# Sheet1.net
KiCad netlist of a schematic drawn in Altium Designer
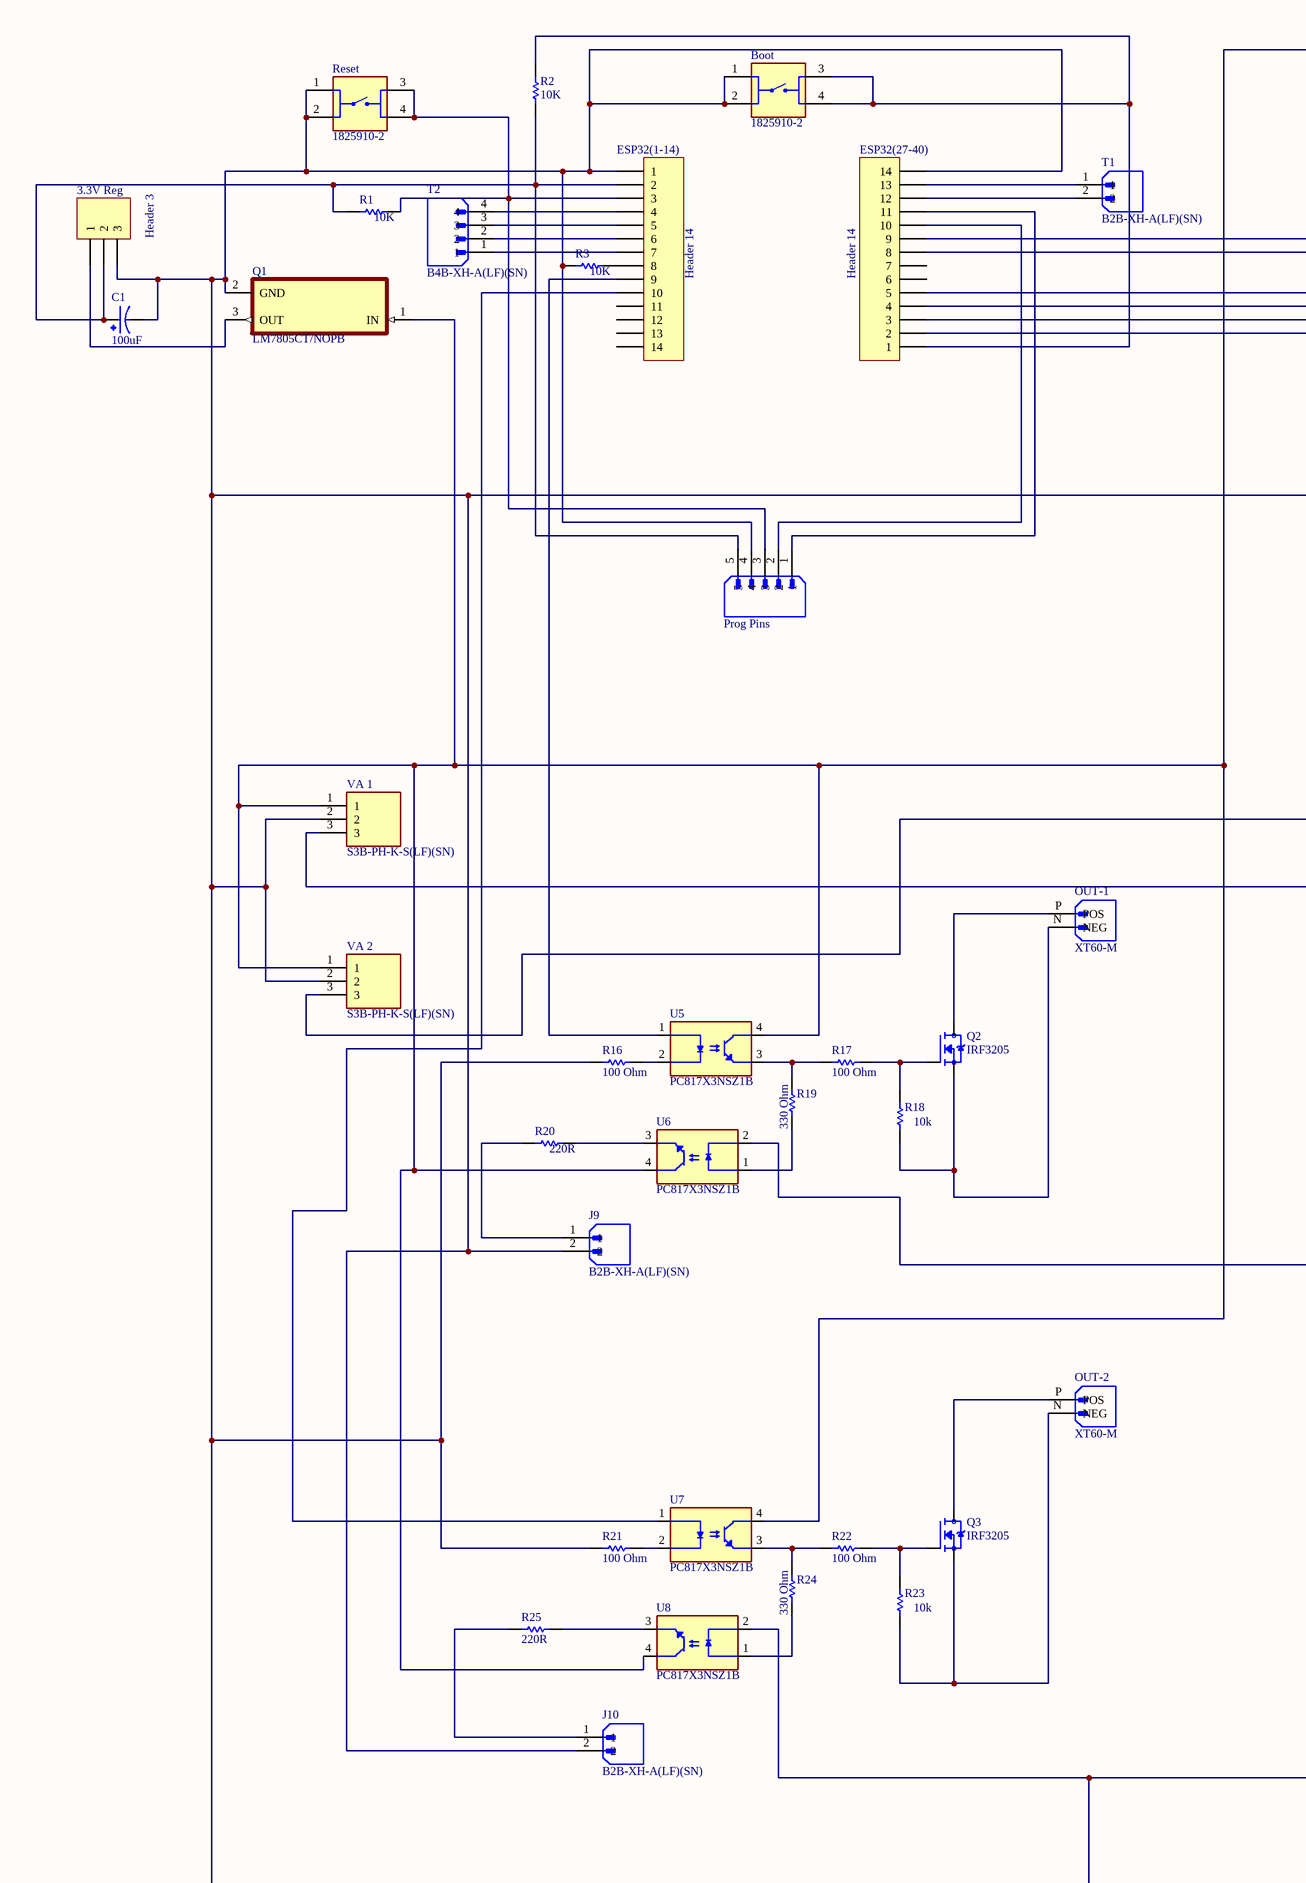
[diagram p0: Sheet1.SchDoc, left]
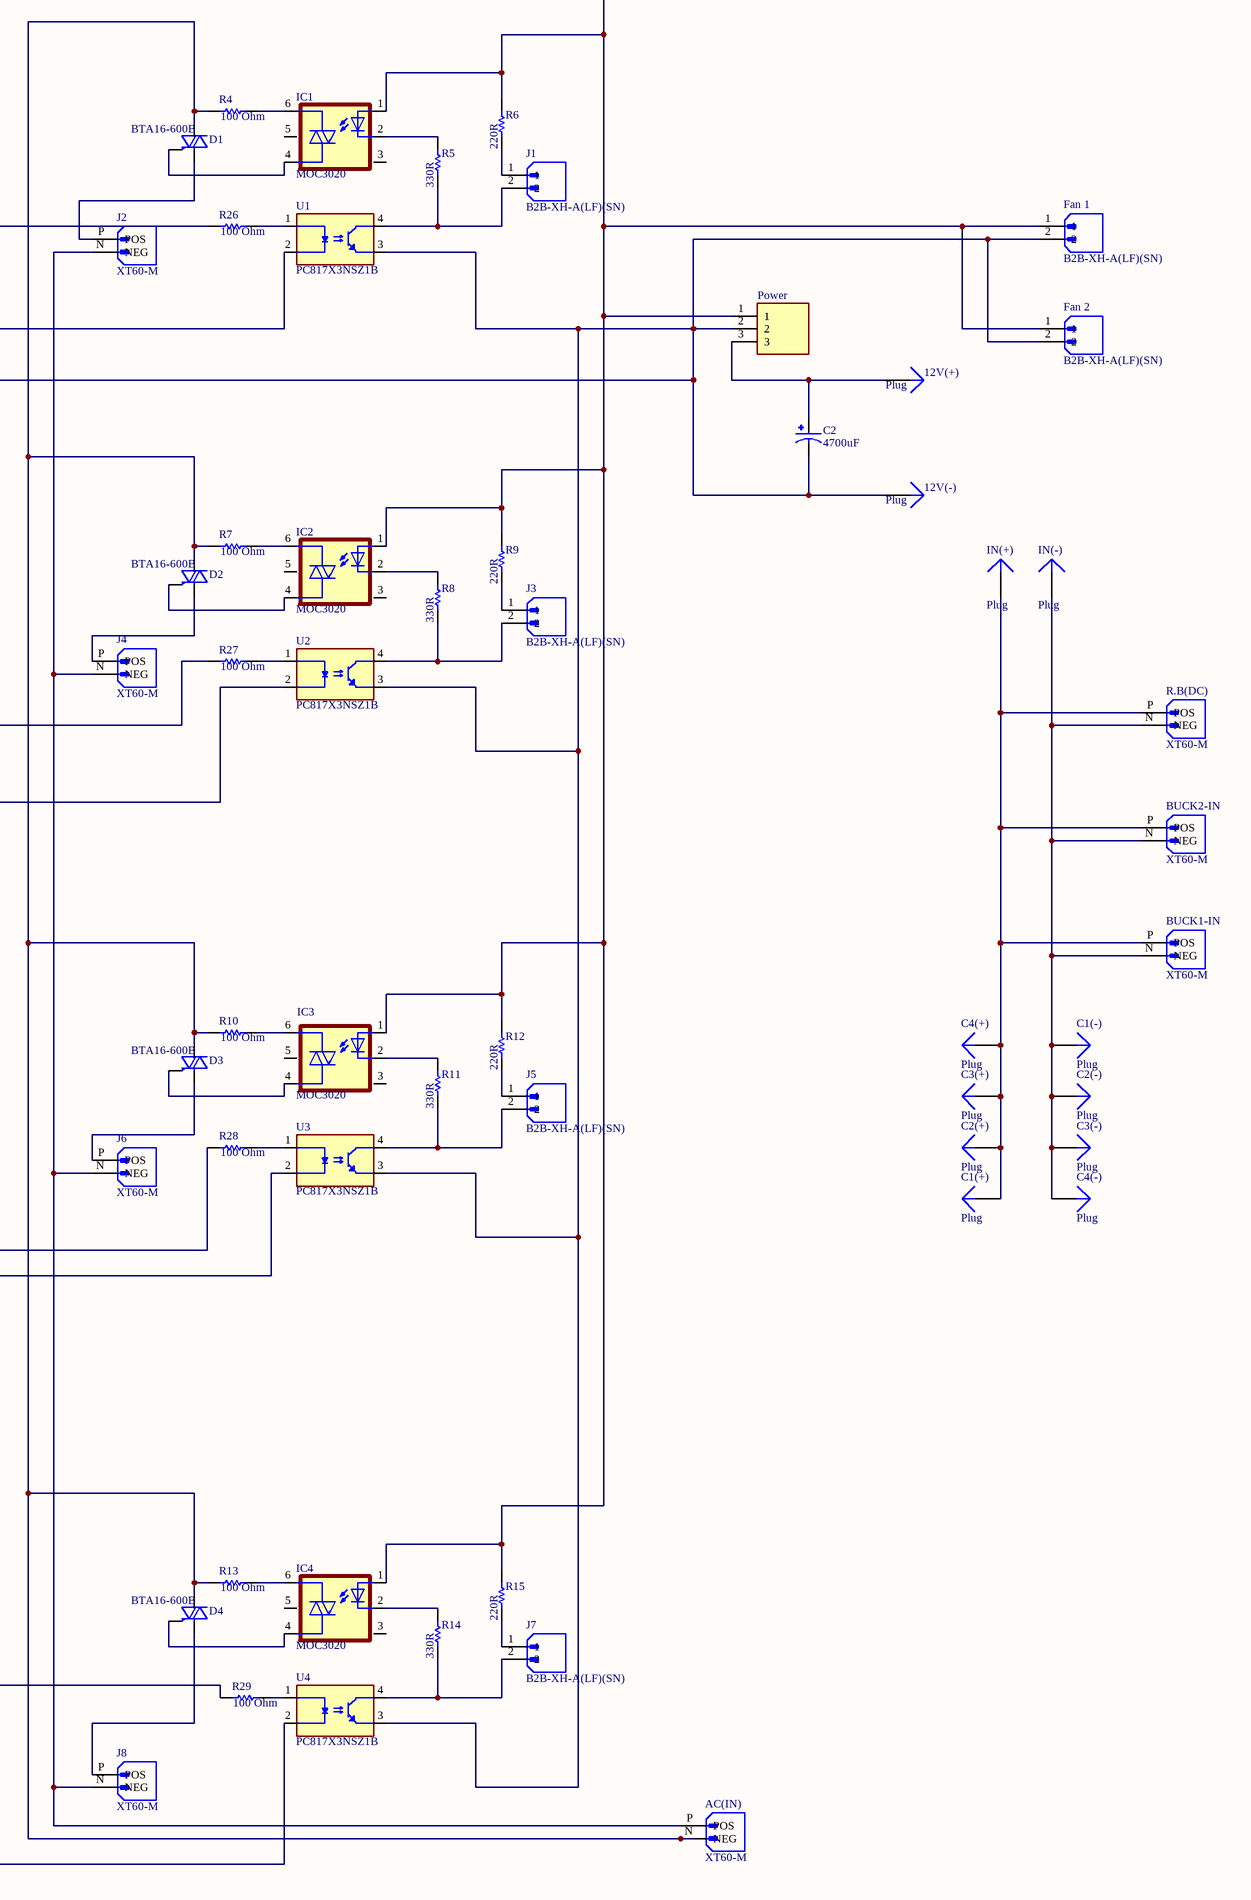
[diagram p1: Sheet1.SchDoc, right]

(export (version "E")
  (design (tool "Eeschema 10.0.6"))
  (components
    (comp (ref "3.3V Reg")
      (value "Header 3")
      (footprint "HDR1X3")
      (description "Header, 3-Pin")
      (fields (field (name "PUBLISHER") "Altium Limited"))
      (libsource (lib "Miscellaneous Connectors") (part "Header 3"))
    )
    (comp (ref "12V(+)")
      (value "Plug")
      (footprint "PIN1")
      (fields (field (name "PUBLISHER") "Altium Limited"))
      (libsource (lib "Miscellaneous Connectors") (part "Plug"))
    )
    (comp (ref "12V(-)")
      (value "Plug")
      (footprint "PIN1")
      (fields (field (name "PUBLISHER") "Altium Limited"))
      (libsource (lib "Miscellaneous Connectors") (part "Plug"))
    )
    (comp (ref "AC(IN)")
      (value "XT60-M")
      (footprint "AMASS_XT60-M")
      (description "Plug; DC supply; XT60; male; PIN: 2; for cable; soldered; 30A; 500V")
      (fields (field (name "MF") "AMASS"))
      (libsource (lib "XT60-M") (part "XT60-M"))
    )
    (comp (ref "Boot")
      (value "1825910-2")
      (footprint "TE_1825910-2")
      (description "50 mA SPST Round Actuator 160 Gram Force Tactile Pushbutton Switch")
      (fields (field (name "MF") "TE Connectivity"))
      (libsource (lib "push button") (part "1825910-2"))
    )
    (comp (ref "BUCK1-IN")
      (value "XT60-M")
      (footprint "AMASS_XT60-M")
      (description "Plug; DC supply; XT60; male; PIN: 2; for cable; soldered; 30A; 500V")
      (fields (field (name "MF") "AMASS"))
      (libsource (lib "XT60-M") (part "XT60-M"))
    )
    (comp (ref "BUCK2-IN")
      (value "XT60-M")
      (footprint "AMASS_XT60-M")
      (description "Plug; DC supply; XT60; male; PIN: 2; for cable; soldered; 30A; 500V")
      (fields (field (name "MF") "AMASS"))
      (libsource (lib "XT60-M") (part "XT60-M"))
    )
    (comp (ref "C1")
      (value "100uF")
      (footprint "CAPPRD250W50D630H1500")
      (description "CAP ALUM 100UF 20% 25V RADIAL")
      (fields (field (name "MP") "EEUEB1E101") (field (name "MF") "Panasonic"))
      (libsource (lib "100uF") (part "EEUEB1E101"))
    )
    (comp (ref "C1(+)")
      (value "Plug")
      (footprint "PIN1")
      (fields (field (name "PUBLISHER") "Altium Limited"))
      (libsource (lib "Miscellaneous Connectors") (part "Plug"))
    )
    (comp (ref "C1(-)")
      (value "Plug")
      (footprint "PIN1")
      (fields (field (name "PUBLISHER") "Altium Limited"))
      (libsource (lib "Miscellaneous Connectors") (part "Plug"))
    )
    (comp (ref "C2")
      (value "4700uF")
      (footprint "CAPPRD750W80D1800H3150")
      (description "CAP ALUM 4700UF 20% 25V RADIAL")
      (fields (field (name "MF") "Panasonic") (field (name "MP") "EEU-TP1E472"))
      (libsource (lib "4700uF") (part "EEUTP1E472"))
    )
    (comp (ref "C2(+)")
      (value "Plug")
      (footprint "PIN1")
      (fields (field (name "PUBLISHER") "Altium Limited"))
      (libsource (lib "Miscellaneous Connectors") (part "Plug"))
    )
    (comp (ref "C2(-)")
      (value "Plug")
      (footprint "PIN1")
      (fields (field (name "PUBLISHER") "Altium Limited"))
      (libsource (lib "Miscellaneous Connectors") (part "Plug"))
    )
    (comp (ref "C3(+)")
      (value "Plug")
      (footprint "PIN1")
      (fields (field (name "PUBLISHER") "Altium Limited"))
      (libsource (lib "Miscellaneous Connectors") (part "Plug"))
    )
    (comp (ref "C3(-)")
      (value "Plug")
      (footprint "PIN1")
      (fields (field (name "PUBLISHER") "Altium Limited"))
      (libsource (lib "Miscellaneous Connectors") (part "Plug"))
    )
    (comp (ref "C4(+)")
      (value "Plug")
      (footprint "PIN1")
      (fields (field (name "PUBLISHER") "Altium Limited"))
      (libsource (lib "Miscellaneous Connectors") (part "Plug"))
    )
    (comp (ref "C4(-)")
      (value "Plug")
      (footprint "PIN1")
      (fields (field (name "PUBLISHER") "Altium Limited"))
      (libsource (lib "Miscellaneous Connectors") (part "Plug"))
    )
    (comp (ref "D1")
      (value "BTA16-600B")
      (footprint "TO255P1040X460X1975-3")
      (description "TRIAC Standard 600V 16A Through Hole IITO-220E")
      (libsource (lib "BTA16-600B") (part "BTA16-600B"))
    )
    (comp (ref "D2")
      (value "BTA16-600B")
      (footprint "TO255P1040X460X1975-3")
      (description "TRIAC Standard 600V 16A Through Hole IITO-220E")
      (libsource (lib "BTA16-600B") (part "BTA16-600B"))
    )
    (comp (ref "D3")
      (value "BTA16-600B")
      (footprint "TO255P1040X460X1975-3")
      (description "TRIAC Standard 600V 16A Through Hole IITO-220E")
      (libsource (lib "BTA16-600B") (part "BTA16-600B"))
    )
    (comp (ref "D4")
      (value "BTA16-600B")
      (footprint "TO255P1040X460X1975-3")
      (description "TRIAC Standard 600V 16A Through Hole IITO-220E")
      (libsource (lib "BTA16-600B") (part "BTA16-600B"))
    )
    (comp (ref "ESP32(1-14)")
      (value "Header 14")
      (footprint "HDR1X14")
      (description "Header, 14-Pin")
      (fields (field (name "PUBLISHER") "Altium Limited"))
      (libsource (lib "Miscellaneous Connectors") (part "Header 14"))
    )
    (comp (ref "ESP32(27-40)")
      (value "Header 14")
      (footprint "HDR1X14")
      (description "Header, 14-Pin")
      (fields (field (name "PUBLISHER") "Altium Limited"))
      (libsource (lib "") (part "Header 14_1"))
    )
    (comp (ref "Fan 1")
      (value "B2B-XH-A(LF)(SN)")
      (footprint "JST_B2B-XH-A(LF)(SN)")
      (description "Connector Header Through Hole 2 position 0.098 (2.50mm)")
      (fields (field (name "MF") "JST Sales America Inc."))
      (libsource (lib "JST-2") (part "B2B-XH-A(LF)(SN)"))
    )
    (comp (ref "Fan 2")
      (value "B2B-XH-A(LF)(SN)")
      (footprint "JST_B2B-XH-A(LF)(SN)")
      (description "Connector Header Through Hole 2 position 0.098 (2.50mm)")
      (fields (field (name "MF") "JST Sales America Inc."))
      (libsource (lib "JST-2") (part "B2B-XH-A(LF)(SN)"))
    )
    (comp (ref "IC1")
      (value "MOC3020")
      (footprint "DIL06-A")
      (description "Optoisolator Triac Output 5300Vrms 1 Channel 6-DIP")
      (fields (field (name "MF") "ON Semiconductor"))
      (libsource (lib "MOC3020") (part "MOC3020"))
    )
    (comp (ref "IC2")
      (value "MOC3020")
      (footprint "DIL06-A")
      (description "Optoisolator Triac Output 5300Vrms 1 Channel 6-DIP")
      (fields (field (name "MF") "ON Semiconductor"))
      (libsource (lib "MOC3020") (part "MOC3020"))
    )
    (comp (ref "IC3")
      (value "MOC3020")
      (footprint "DIL06-A")
      (description "Optoisolator Triac Output 5300Vrms 1 Channel 6-DIP")
      (fields (field (name "MF") "ON Semiconductor"))
      (libsource (lib "MOC3020") (part "MOC3020"))
    )
    (comp (ref "IC4")
      (value "MOC3020")
      (footprint "DIL06-A")
      (description "Optoisolator Triac Output 5300Vrms 1 Channel 6-DIP")
      (fields (field (name "MF") "ON Semiconductor"))
      (libsource (lib "MOC3020") (part "MOC3020"))
    )
    (comp (ref "IN(+)")
      (value "Plug")
      (footprint "PIN1")
      (fields (field (name "PUBLISHER") "Altium Limited"))
      (libsource (lib "Miscellaneous Connectors") (part "Plug"))
    )
    (comp (ref "IN(-)")
      (value "Plug")
      (footprint "PIN1")
      (fields (field (name "PUBLISHER") "Altium Limited"))
      (libsource (lib "Miscellaneous Connectors") (part "Plug"))
    )
    (comp (ref "J1")
      (value "B2B-XH-A(LF)(SN)")
      (footprint "JST_B2B-XH-A(LF)(SN)")
      (description "Connector Header Through Hole 2 position 0.098 (2.50mm)")
      (fields (field (name "MF") "JST Sales America Inc."))
      (libsource (lib "JST-2") (part "B2B-XH-A(LF)(SN)"))
    )
    (comp (ref "J2")
      (value "XT60-M")
      (footprint "AMASS_XT60-M")
      (description "Plug; DC supply; XT60; male; PIN: 2; for cable; soldered; 30A; 500V")
      (fields (field (name "MF") "AMASS"))
      (libsource (lib "XT60-M") (part "XT60-M"))
    )
    (comp (ref "J3")
      (value "B2B-XH-A(LF)(SN)")
      (footprint "JST_B2B-XH-A(LF)(SN)")
      (description "Connector Header Through Hole 2 position 0.098 (2.50mm)")
      (fields (field (name "MF") "JST Sales America Inc."))
      (libsource (lib "JST-2") (part "B2B-XH-A(LF)(SN)"))
    )
    (comp (ref "J4")
      (value "XT60-M")
      (footprint "AMASS_XT60-M")
      (description "Plug; DC supply; XT60; male; PIN: 2; for cable; soldered; 30A; 500V")
      (fields (field (name "MF") "AMASS"))
      (libsource (lib "XT60-M") (part "XT60-M"))
    )
    (comp (ref "J5")
      (value "B2B-XH-A(LF)(SN)")
      (footprint "JST_B2B-XH-A(LF)(SN)")
      (description "Connector Header Through Hole 2 position 0.098 (2.50mm)")
      (fields (field (name "MF") "JST Sales America Inc."))
      (libsource (lib "JST-2") (part "B2B-XH-A(LF)(SN)"))
    )
    (comp (ref "J6")
      (value "XT60-M")
      (footprint "AMASS_XT60-M")
      (description "Plug; DC supply; XT60; male; PIN: 2; for cable; soldered; 30A; 500V")
      (fields (field (name "MF") "AMASS"))
      (libsource (lib "XT60-M") (part "XT60-M"))
    )
    (comp (ref "J7")
      (value "B2B-XH-A(LF)(SN)")
      (footprint "JST_B2B-XH-A(LF)(SN)")
      (description "Connector Header Through Hole 2 position 0.098 (2.50mm)")
      (fields (field (name "MF") "JST Sales America Inc."))
      (libsource (lib "JST-2") (part "B2B-XH-A(LF)(SN)"))
    )
    (comp (ref "J8")
      (value "XT60-M")
      (footprint "AMASS_XT60-M")
      (description "Plug; DC supply; XT60; male; PIN: 2; for cable; soldered; 30A; 500V")
      (fields (field (name "MF") "AMASS"))
      (libsource (lib "XT60-M") (part "XT60-M"))
    )
    (comp (ref "J9")
      (value "B2B-XH-A(LF)(SN)")
      (footprint "JST_B2B-XH-A(LF)(SN)")
      (description "Connector Header Through Hole 2 position 0.098 (2.50mm)")
      (fields (field (name "MF") "JST Sales America Inc."))
      (libsource (lib "JST-2") (part "B2B-XH-A(LF)(SN)"))
    )
    (comp (ref "J10")
      (value "B2B-XH-A(LF)(SN)")
      (footprint "JST_B2B-XH-A(LF)(SN)")
      (description "Connector Header Through Hole 2 position 0.098 (2.50mm)")
      (fields (field (name "MF") "JST Sales America Inc."))
      (libsource (lib "JST-2") (part "B2B-XH-A(LF)(SN)"))
    )
    (comp (ref "OUT-1")
      (value "XT60-M")
      (footprint "AMASS_XT60-M")
      (description "Plug; DC supply; XT60; male; PIN: 2; for cable; soldered; 30A; 500V")
      (fields (field (name "MF") "AMASS"))
      (libsource (lib "XT60-M") (part "XT60-M"))
    )
    (comp (ref "OUT-2")
      (value "XT60-M")
      (footprint "AMASS_XT60-M")
      (description "Plug; DC supply; XT60; male; PIN: 2; for cable; soldered; 30A; 500V")
      (fields (field (name "MF") "AMASS"))
      (libsource (lib "XT60-M") (part "XT60-M"))
    )
    (comp (ref "Power")
      (value "~")
      (footprint "JST_S3B-PH-K-S(LF)(SN)")
      (description "Connector Header Through Hole, Right Angle 3 position 0.079\" (2.00mm)")
      (fields (field (name "MP") "S3B-PH-K-S(LF)(SN)"))
      (libsource (lib "JST-3") (part "S3B-PH-K-S(LF)(SN)"))
    )
    (comp (ref "Prog Pins")
      (value "~")
      (footprint "JST_B5B-XH-A(LF)(SN)")
      (description "Connector Header Through Hole 5 position 0.098 (2.50mm)")
      (fields (field (name "MP") "B5B-XH-A(LF)(SN)") (field (name "MF") "JST Sales America Inc."))
      (libsource (lib "JST-5") (part "B5B-XH-A(LF)(SN)"))
    )
    (comp (ref "Q1")
      (value "LM7805CT/NOPB")
      (footprint "TO254P1054X470X1955-3")
      (libsource (lib "LM7805CT_NOPB") (part "LM7805CT/NOPB"))
    )
    (comp (ref "Q2")
      (value "IRF3205")
      (footprint "TO254P1041X444X2933-3")
      (description "N-Channel 55V 110A (Tc) 200W (Tc) Through Hole TO-220AB")
      (fields (field (name "MF") "Infineon Technologies"))
      (libsource (lib "IRF3205") (part "IRF3205"))
    )
    (comp (ref "Q3")
      (value "IRF3205")
      (footprint "TO254P1041X444X2933-3")
      (description "N-Channel 55V 110A (Tc) 200W (Tc) Through Hole TO-220AB")
      (fields (field (name "MF") "Infineon Technologies"))
      (libsource (lib "IRF3205") (part "IRF3205"))
    )
    (comp (ref "R.B(DC)")
      (value "XT60-M")
      (footprint "AMASS_XT60-M")
      (description "Plug; DC supply; XT60; male; PIN: 2; for cable; soldered; 30A; 500V")
      (fields (field (name "MF") "AMASS"))
      (libsource (lib "XT60-M") (part "XT60-M"))
    )
    (comp (ref "R1")
      (value "10K")
      (footprint "AXIAL-0.3")
      (description "Resistor")
      (fields (field (name "PUBLISHER") "Altium Limited"))
      (libsource (lib "Miscellaneous Devices") (part "Res1"))
    )
    (comp (ref "R2")
      (value "10K")
      (footprint "AXIAL-0.3")
      (description "Resistor")
      (fields (field (name "PUBLISHER") "Altium Limited"))
      (libsource (lib "Miscellaneous Devices") (part "Res1"))
    )
    (comp (ref "R3")
      (value "10K")
      (footprint "AXIAL-0.3")
      (description "Resistor")
      (fields (field (name "PUBLISHER") "Altium Limited"))
      (libsource (lib "Miscellaneous Devices") (part "Res1"))
    )
    (comp (ref "R4")
      (value "100 Ohm")
      (footprint "AXIAL-0.3")
      (description "Resistor")
      (fields (field (name "PUBLISHER") "Altium Limited"))
      (libsource (lib "Miscellaneous Devices") (part "Res1"))
    )
    (comp (ref "R5")
      (value "330R")
      (footprint "AXIAL-0.3")
      (description "Resistor")
      (fields (field (name "PUBLISHER") "Altium Limited"))
      (libsource (lib "Miscellaneous Devices") (part "Res1"))
    )
    (comp (ref "R6")
      (value "220R")
      (footprint "AXIAL-0.3")
      (description "Resistor")
      (fields (field (name "PUBLISHER") "Altium Limited"))
      (libsource (lib "Miscellaneous Devices") (part "Res1"))
    )
    (comp (ref "R7")
      (value "100 Ohm")
      (footprint "AXIAL-0.3")
      (description "Resistor")
      (fields (field (name "PUBLISHER") "Altium Limited"))
      (libsource (lib "Miscellaneous Devices") (part "Res1"))
    )
    (comp (ref "R8")
      (value "330R")
      (footprint "AXIAL-0.3")
      (description "Resistor")
      (fields (field (name "PUBLISHER") "Altium Limited"))
      (libsource (lib "Miscellaneous Devices") (part "Res1"))
    )
    (comp (ref "R9")
      (value "220R")
      (footprint "AXIAL-0.3")
      (description "Resistor")
      (fields (field (name "PUBLISHER") "Altium Limited"))
      (libsource (lib "Miscellaneous Devices") (part "Res1"))
    )
    (comp (ref "R10")
      (value "100 Ohm")
      (footprint "AXIAL-0.3")
      (description "Resistor")
      (fields (field (name "PUBLISHER") "Altium Limited"))
      (libsource (lib "Miscellaneous Devices") (part "Res1"))
    )
    (comp (ref "R11")
      (value "330R")
      (footprint "AXIAL-0.3")
      (description "Resistor")
      (fields (field (name "PUBLISHER") "Altium Limited"))
      (libsource (lib "Miscellaneous Devices") (part "Res1"))
    )
    (comp (ref "R12")
      (value "220R")
      (footprint "AXIAL-0.3")
      (description "Resistor")
      (fields (field (name "PUBLISHER") "Altium Limited"))
      (libsource (lib "Miscellaneous Devices") (part "Res1"))
    )
    (comp (ref "R13")
      (value "100 Ohm")
      (footprint "AXIAL-0.3")
      (description "Resistor")
      (fields (field (name "PUBLISHER") "Altium Limited"))
      (libsource (lib "Miscellaneous Devices") (part "Res1"))
    )
    (comp (ref "R14")
      (value "330R")
      (footprint "AXIAL-0.3")
      (description "Resistor")
      (fields (field (name "PUBLISHER") "Altium Limited"))
      (libsource (lib "Miscellaneous Devices") (part "Res1"))
    )
    (comp (ref "R15")
      (value "220R")
      (footprint "AXIAL-0.3")
      (description "Resistor")
      (fields (field (name "PUBLISHER") "Altium Limited"))
      (libsource (lib "Miscellaneous Devices") (part "Res1"))
    )
    (comp (ref "R16")
      (value "100 Ohm")
      (footprint "AXIAL-0.3")
      (description "Resistor")
      (fields (field (name "PUBLISHER") "Altium Limited"))
      (libsource (lib "Miscellaneous Devices") (part "Res1"))
    )
    (comp (ref "R17")
      (value "100 Ohm")
      (footprint "AXIAL-0.3")
      (description "Resistor")
      (fields (field (name "PUBLISHER") "Altium Limited"))
      (libsource (lib "Miscellaneous Devices") (part "Res1"))
    )
    (comp (ref "R18")
      (value "10k")
      (footprint "AXIAL-0.3")
      (description "Resistor")
      (fields (field (name "PUBLISHER") "Altium Limited"))
      (libsource (lib "Miscellaneous Devices") (part "Res1"))
    )
    (comp (ref "R19")
      (value "330 Ohm")
      (footprint "AXIAL-0.3")
      (description "Resistor")
      (fields (field (name "PUBLISHER") "Altium Limited"))
      (libsource (lib "Miscellaneous Devices") (part "Res1"))
    )
    (comp (ref "R20")
      (value "220R")
      (footprint "AXIAL-0.3")
      (description "Resistor")
      (fields (field (name "PUBLISHER") "Altium Limited"))
      (libsource (lib "Miscellaneous Devices") (part "Res1"))
    )
    (comp (ref "R21")
      (value "100 Ohm")
      (footprint "AXIAL-0.3")
      (description "Resistor")
      (fields (field (name "PUBLISHER") "Altium Limited"))
      (libsource (lib "Miscellaneous Devices") (part "Res1"))
    )
    (comp (ref "R22")
      (value "100 Ohm")
      (footprint "AXIAL-0.3")
      (description "Resistor")
      (fields (field (name "PUBLISHER") "Altium Limited"))
      (libsource (lib "Miscellaneous Devices") (part "Res1"))
    )
    (comp (ref "R23")
      (value "10k")
      (footprint "AXIAL-0.3")
      (description "Resistor")
      (fields (field (name "PUBLISHER") "Altium Limited"))
      (libsource (lib "Miscellaneous Devices") (part "Res1"))
    )
    (comp (ref "R24")
      (value "330 Ohm")
      (footprint "AXIAL-0.3")
      (description "Resistor")
      (fields (field (name "PUBLISHER") "Altium Limited"))
      (libsource (lib "Miscellaneous Devices") (part "Res1"))
    )
    (comp (ref "R25")
      (value "220R")
      (footprint "AXIAL-0.3")
      (description "Resistor")
      (fields (field (name "PUBLISHER") "Altium Limited"))
      (libsource (lib "Miscellaneous Devices") (part "Res1"))
    )
    (comp (ref "R26")
      (value "100 Ohm")
      (footprint "AXIAL-0.3")
      (description "Resistor")
      (fields (field (name "PUBLISHER") "Altium Limited"))
      (libsource (lib "Miscellaneous Devices") (part "Res1"))
    )
    (comp (ref "R27")
      (value "100 Ohm")
      (footprint "AXIAL-0.3")
      (description "Resistor")
      (fields (field (name "PUBLISHER") "Altium Limited"))
      (libsource (lib "Miscellaneous Devices") (part "Res1"))
    )
    (comp (ref "R28")
      (value "100 Ohm")
      (footprint "AXIAL-0.3")
      (description "Resistor")
      (fields (field (name "PUBLISHER") "Altium Limited"))
      (libsource (lib "Miscellaneous Devices") (part "Res1"))
    )
    (comp (ref "R29")
      (value "100 Ohm")
      (footprint "AXIAL-0.3")
      (description "Resistor")
      (fields (field (name "PUBLISHER") "Altium Limited"))
      (libsource (lib "Miscellaneous Devices") (part "Res1"))
    )
    (comp (ref "Reset")
      (value "1825910-2")
      (footprint "TE_1825910-2")
      (description "50 mA SPST Round Actuator 160 Gram Force Tactile Pushbutton Switch")
      (fields (field (name "MF") "TE Connectivity"))
      (libsource (lib "push button") (part "1825910-2"))
    )
    (comp (ref "T1")
      (value "B2B-XH-A(LF)(SN)")
      (footprint "JST_B2B-XH-A(LF)(SN)")
      (description "Connector Header Through Hole 2 position 0.098 (2.50mm)")
      (fields (field (name "MF") "JST Sales America Inc."))
      (libsource (lib "JST-2") (part "B2B-XH-A(LF)(SN)"))
    )
    (comp (ref "T2")
      (value "B4B-XH-A(LF)(SN)")
      (footprint "JST_B4B-XH-A(LF)(SN)")
      (description "Connector Header Through Hole 4 position 0.098 (2.50mm)")
      (fields (field (name "MF") "JST Sales"))
      (libsource (lib "JST-4") (part "B4B-XH-A(LF)(SN)"))
    )
    (comp (ref "U1")
      (value "PC817X3NSZ1B")
      (footprint "DIP762W50P254L495H455Q4")
      (description "Optoisolator Transistor Output - 1 Channel 4-DIP")
      (fields (field (name "MF") "Sharp Microelectronics"))
      (libsource (lib "PC817X3NSZ1B") (part "PC817X3NSZ1B"))
    )
    (comp (ref "U2")
      (value "PC817X3NSZ1B")
      (footprint "DIP762W50P254L495H455Q4")
      (description "Optoisolator Transistor Output - 1 Channel 4-DIP")
      (fields (field (name "MF") "Sharp Microelectronics"))
      (libsource (lib "PC817X3NSZ1B") (part "PC817X3NSZ1B"))
    )
    (comp (ref "U3")
      (value "PC817X3NSZ1B")
      (footprint "DIP762W50P254L495H455Q4")
      (description "Optoisolator Transistor Output - 1 Channel 4-DIP")
      (fields (field (name "MF") "Sharp Microelectronics"))
      (libsource (lib "PC817X3NSZ1B") (part "PC817X3NSZ1B"))
    )
    (comp (ref "U4")
      (value "PC817X3NSZ1B")
      (footprint "DIP762W50P254L495H455Q4")
      (description "Optoisolator Transistor Output - 1 Channel 4-DIP")
      (fields (field (name "MF") "Sharp Microelectronics"))
      (libsource (lib "PC817X3NSZ1B") (part "PC817X3NSZ1B"))
    )
    (comp (ref "U5")
      (value "PC817X3NSZ1B")
      (footprint "DIP762W50P254L495H455Q4")
      (description "Optoisolator Transistor Output - 1 Channel 4-DIP")
      (fields (field (name "MF") "Sharp Microelectronics"))
      (libsource (lib "PC817X3NSZ1B") (part "PC817X3NSZ1B"))
    )
    (comp (ref "U6")
      (value "PC817X3NSZ1B")
      (footprint "DIP762W50P254L495H455Q4")
      (description "Optoisolator Transistor Output - 1 Channel 4-DIP")
      (fields (field (name "MF") "Sharp Microelectronics"))
      (libsource (lib "") (part "PC817X3NSZ1B_1"))
    )
    (comp (ref "U7")
      (value "PC817X3NSZ1B")
      (footprint "DIP762W50P254L495H455Q4")
      (description "Optoisolator Transistor Output - 1 Channel 4-DIP")
      (fields (field (name "MF") "Sharp Microelectronics"))
      (libsource (lib "PC817X3NSZ1B") (part "PC817X3NSZ1B"))
    )
    (comp (ref "U8")
      (value "PC817X3NSZ1B")
      (footprint "DIP762W50P254L495H455Q4")
      (description "Optoisolator Transistor Output - 1 Channel 4-DIP")
      (fields (field (name "MF") "Sharp Microelectronics"))
      (libsource (lib "") (part "PC817X3NSZ1B_1"))
    )
    (comp (ref "VA 1")
      (value "S3B-PH-K-S(LF)(SN)")
      (footprint "JST_S3B-PH-K-S(LF)(SN)")
      (description "Connector Header Through Hole, Right Angle 3 position 0.079\" (2.00mm)")
      (libsource (lib "JST-3") (part "S3B-PH-K-S(LF)(SN)"))
    )
    (comp (ref "VA 2")
      (value "S3B-PH-K-S(LF)(SN)")
      (footprint "JST_S3B-PH-K-S(LF)(SN)")
      (description "Connector Header Through Hole, Right Angle 3 position 0.079\" (2.00mm)")
      (libsource (lib "JST-3") (part "S3B-PH-K-S(LF)(SN)"))
    )
  )
  (nets
    (net (code "1") (name "Net-(3.3V Reg-Pad2)") (class "Default")
      (node (ref "3.3V Reg") (pin "2") (pinfunction "2_2") (pintype "passive"))
      (node (ref "C1") (pin "P") (pinfunction "P_P") (pintype "passive"))
      (node (ref "ESP32(1-14)") (pin "2") (pinfunction "2_2") (pintype "passive"))
      (node (ref "Prog Pins") (pin "5") (pinfunction "5_5") (pintype "passive"))
      (node (ref "R1") (pin "1") (pinfunction "1_1") (pintype "passive"))
      (node (ref "R2") (pin "1") (pinfunction "1_1") (pintype "passive"))
    )
    (net (code "2") (name "Net-(12V(+)-Pad1)") (class "Default")
      (node (ref "12V(+)") (pin "1") (pinfunction "1_1") (pintype "passive"))
      (node (ref "C2") (pin "P") (pinfunction "P_P") (pintype "passive"))
      (node (ref "Power") (pin "3") (pinfunction "3_3") (pintype "passive"))
    )
    (net (code "3") (name "Net-(AC(IN)-NEG)") (class "Default")
      (node (ref "AC(IN)") (pin "N") (pinfunction "NEG_N") (pintype "passive"))
      (node (ref "D1") (pin "2") (pinfunction "A2_2") (pintype "passive"))
      (node (ref "D2") (pin "2") (pinfunction "A2_2") (pintype "passive"))
      (node (ref "D3") (pin "2") (pinfunction "A2_2") (pintype "passive"))
      (node (ref "D4") (pin "2") (pinfunction "A2_2") (pintype "passive"))
      (node (ref "R10") (pin "1") (pinfunction "1_1") (pintype "passive"))
      (node (ref "R13") (pin "1") (pinfunction "1_1") (pintype "passive"))
      (node (ref "R4") (pin "1") (pinfunction "1_1") (pintype "passive"))
      (node (ref "R7") (pin "1") (pinfunction "1_1") (pintype "passive"))
    )
    (net (code "4") (name "Net-(AC(IN)-POS)") (class "Default")
      (node (ref "AC(IN)") (pin "P") (pinfunction "POS_P") (pintype "passive"))
      (node (ref "J2") (pin "N") (pinfunction "NEG_N") (pintype "passive"))
      (node (ref "J4") (pin "N") (pinfunction "NEG_N") (pintype "passive"))
      (node (ref "J6") (pin "N") (pinfunction "NEG_N") (pintype "passive"))
      (node (ref "J8") (pin "N") (pinfunction "NEG_N") (pintype "passive"))
    )
    (net (code "5") (name "Net-(BUCK1-IN-NEG)") (class "Default")
      (node (ref "BUCK1-IN") (pin "N") (pinfunction "NEG_N") (pintype "passive"))
      (node (ref "BUCK2-IN") (pin "N") (pinfunction "NEG_N") (pintype "passive"))
      (node (ref "C1(-)") (pin "1") (pinfunction "1_1") (pintype "passive"))
      (node (ref "C2(-)") (pin "1") (pinfunction "1_1") (pintype "passive"))
      (node (ref "C3(-)") (pin "1") (pinfunction "1_1") (pintype "passive"))
      (node (ref "C4(-)") (pin "1") (pinfunction "1_1") (pintype "passive"))
      (node (ref "IN(-)") (pin "1") (pinfunction "1_1") (pintype "passive"))
      (node (ref "R.B(DC)") (pin "N") (pinfunction "NEG_N") (pintype "passive"))
    )
    (net (code "6") (name "Net-(BUCK1-IN-POS)") (class "Default")
      (node (ref "BUCK1-IN") (pin "P") (pinfunction "POS_P") (pintype "passive"))
      (node (ref "BUCK2-IN") (pin "P") (pinfunction "POS_P") (pintype "passive"))
      (node (ref "C1(+)") (pin "1") (pinfunction "1_1") (pintype "passive"))
      (node (ref "C2(+)") (pin "1") (pinfunction "1_1") (pintype "passive"))
      (node (ref "C3(+)") (pin "1") (pinfunction "1_1") (pintype "passive"))
      (node (ref "C4(+)") (pin "1") (pinfunction "1_1") (pintype "passive"))
      (node (ref "IN(+)") (pin "1") (pinfunction "1_1") (pintype "passive"))
      (node (ref "R.B(DC)") (pin "P") (pinfunction "POS_P") (pintype "passive"))
    )
    (net (code "7") (name "Net-(Boot-Pad3)") (class "Default")
      (node (ref "Boot") (pin "3") (pinfunction "3_3") (pintype "passive"))
      (node (ref "Boot") (pin "4") (pinfunction "4_4") (pintype "passive"))
      (node (ref "ESP32(27-40)") (pin "1") (pinfunction "1_1") (pintype "passive"))
      (node (ref "R2") (pin "2") (pinfunction "2_2") (pintype "passive"))
    )
    (net (code "8") (name "Net-(D1-A1)") (class "Default")
      (node (ref "D1") (pin "1") (pinfunction "A1_1") (pintype "passive"))
      (node (ref "J2") (pin "P") (pinfunction "POS_P") (pintype "passive"))
    )
    (net (code "9") (name "Net-(D1-G)") (class "Default")
      (node (ref "D1") (pin "3") (pinfunction "G_3") (pintype "passive"))
      (node (ref "IC1") (pin "4") (pinfunction "A1_4") (pintype "passive"))
    )
    (net (code "10") (name "Net-(D2-A1)") (class "Default")
      (node (ref "D2") (pin "1") (pinfunction "A1_1") (pintype "passive"))
      (node (ref "J4") (pin "P") (pinfunction "POS_P") (pintype "passive"))
    )
    (net (code "11") (name "Net-(D2-G)") (class "Default")
      (node (ref "D2") (pin "3") (pinfunction "G_3") (pintype "passive"))
      (node (ref "IC2") (pin "4") (pinfunction "A1_4") (pintype "passive"))
    )
    (net (code "12") (name "Net-(D3-A1)") (class "Default")
      (node (ref "D3") (pin "1") (pinfunction "A1_1") (pintype "passive"))
      (node (ref "J6") (pin "P") (pinfunction "POS_P") (pintype "passive"))
    )
    (net (code "13") (name "Net-(D3-G)") (class "Default")
      (node (ref "D3") (pin "3") (pinfunction "G_3") (pintype "passive"))
      (node (ref "IC3") (pin "4") (pinfunction "A1_4") (pintype "passive"))
    )
    (net (code "14") (name "Net-(D4-A1)") (class "Default")
      (node (ref "D4") (pin "1") (pinfunction "A1_1") (pintype "passive"))
      (node (ref "J8") (pin "P") (pinfunction "POS_P") (pintype "passive"))
    )
    (net (code "15") (name "Net-(D4-G)") (class "Default")
      (node (ref "D4") (pin "3") (pinfunction "G_3") (pintype "passive"))
      (node (ref "IC4") (pin "4") (pinfunction "A1_4") (pintype "passive"))
    )
    (net (code "16") (name "Net-(ESP32(1-14)-Pad3)") (class "Default")
      (node (ref "ESP32(1-14)") (pin "3") (pinfunction "3_3") (pintype "passive"))
      (node (ref "Prog Pins") (pin "3") (pinfunction "3_3") (pintype "passive"))
      (node (ref "R1") (pin "2") (pinfunction "2_2") (pintype "passive"))
      (node (ref "Reset") (pin "3") (pinfunction "3_3") (pintype "passive"))
      (node (ref "Reset") (pin "4") (pinfunction "4_4") (pintype "passive"))
    )
    (net (code "17") (name "Net-(ESP32(1-14)-Pad4)") (class "Default")
      (node (ref "ESP32(1-14)") (pin "4") (pinfunction "4_4") (pintype "passive"))
      (node (ref "T2") (pin "4") (pinfunction "4_4") (pintype "passive"))
    )
    (net (code "18") (name "Net-(ESP32(1-14)-Pad5)") (class "Default")
      (node (ref "ESP32(1-14)") (pin "5") (pinfunction "5_5") (pintype "passive"))
      (node (ref "T2") (pin "3") (pinfunction "3_3") (pintype "passive"))
    )
    (net (code "19") (name "Net-(ESP32(1-14)-Pad6)") (class "Default")
      (node (ref "ESP32(1-14)") (pin "6") (pinfunction "6_6") (pintype "passive"))
      (node (ref "T2") (pin "2") (pinfunction "2_2") (pintype "passive"))
    )
    (net (code "20") (name "Net-(ESP32(1-14)-Pad7)") (class "Default")
      (node (ref "ESP32(1-14)") (pin "7") (pinfunction "7_7") (pintype "passive"))
      (node (ref "T2") (pin "1") (pinfunction "1_1") (pintype "passive"))
    )
    (net (code "21") (name "Net-(ESP32(1-14)-Pad8)") (class "Default")
      (node (ref "ESP32(1-14)") (pin "8") (pinfunction "8_8") (pintype "passive"))
      (node (ref "R3") (pin "2") (pinfunction "2_2") (pintype "passive"))
    )
    (net (code "22") (name "Net-(ESP32(27-40)-Pad2)") (class "Default")
      (node (ref "ESP32(27-40)") (pin "2") (pinfunction "2_2") (pintype "passive"))
      (node (ref "R26") (pin "1") (pinfunction "1_1") (pintype "passive"))
    )
    (net (code "23") (name "Net-(ESP32(27-40)-Pad3)") (class "Default")
      (node (ref "ESP32(27-40)") (pin "3") (pinfunction "3_3") (pintype "passive"))
      (node (ref "R27") (pin "1") (pinfunction "1_1") (pintype "passive"))
    )
    (net (code "24") (name "Net-(ESP32(27-40)-Pad4)") (class "Default")
      (node (ref "ESP32(27-40)") (pin "4") (pinfunction "4_4") (pintype "passive"))
      (node (ref "R28") (pin "1") (pinfunction "1_1") (pintype "passive"))
    )
    (net (code "25") (name "Net-(ESP32(27-40)-Pad5)") (class "Default")
      (node (ref "ESP32(27-40)") (pin "5") (pinfunction "5_5") (pintype "passive"))
      (node (ref "R29") (pin "1") (pinfunction "1_1") (pintype "passive"))
    )
    (net (code "26") (name "Net-(ESP32(27-40)-Pad8)") (class "Default")
      (node (ref "ESP32(27-40)") (pin "8") (pinfunction "8_8") (pintype "passive"))
      (node (ref "VA 1") (pin "3") (pinfunction "3_3") (pintype "passive"))
    )
    (net (code "27") (name "Net-(ESP32(27-40)-Pad9)") (class "Default")
      (node (ref "ESP32(27-40)") (pin "9") (pinfunction "9_9") (pintype "passive"))
      (node (ref "VA 2") (pin "3") (pinfunction "3_3") (pintype "passive"))
    )
    (net (code "28") (name "Net-(ESP32(27-40)-Pad10)") (class "Default")
      (node (ref "ESP32(27-40)") (pin "10") (pinfunction "10_10") (pintype "passive"))
      (node (ref "Prog Pins") (pin "2") (pinfunction "2_2") (pintype "passive"))
    )
    (net (code "29") (name "Net-(ESP32(27-40)-Pad11)") (class "Default")
      (node (ref "ESP32(27-40)") (pin "11") (pinfunction "11_11") (pintype "passive"))
      (node (ref "Prog Pins") (pin "1") (pinfunction "1_1") (pintype "passive"))
    )
    (net (code "30") (name "Net-(ESP32(27-40)-Pad12)") (class "Default")
      (node (ref "ESP32(27-40)") (pin "12") (pinfunction "12_12") (pintype "passive"))
      (node (ref "T1") (pin "2") (pinfunction "2_2") (pintype "passive"))
    )
    (net (code "31") (name "Net-(ESP32(27-40)-Pad13)") (class "Default")
      (node (ref "ESP32(27-40)") (pin "13") (pinfunction "13_13") (pintype "passive"))
      (node (ref "T1") (pin "1") (pinfunction "1_1") (pintype "passive"))
    )
    (net (code "32") (name "Net-(IC1-A)") (class "Default")
      (node (ref "Fan 1") (pin "1") (pinfunction "1_1") (pintype "passive"))
      (node (ref "Fan 2") (pin "1") (pinfunction "1_1") (pintype "passive"))
      (node (ref "IC1") (pin "1") (pinfunction "A_1") (pintype "passive"))
      (node (ref "IC2") (pin "1") (pinfunction "A_1") (pintype "passive"))
      (node (ref "IC3") (pin "1") (pinfunction "A_1") (pintype "passive"))
      (node (ref "IC4") (pin "1") (pinfunction "A_1") (pintype "passive"))
      (node (ref "Power") (pin "1") (pinfunction "1_1") (pintype "passive"))
      (node (ref "Q1") (pin "1") (pinfunction "IN_1") (pintype "input"))
      (node (ref "R12") (pin "2") (pinfunction "2_2") (pintype "passive"))
      (node (ref "R15") (pin "2") (pinfunction "2_2") (pintype "passive"))
      (node (ref "R6") (pin "2") (pinfunction "2_2") (pintype "passive"))
      (node (ref "R9") (pin "2") (pinfunction "2_2") (pintype "passive"))
      (node (ref "U5") (pin "4") (pinfunction "COLLECTOR_4") (pintype "passive"))
      (node (ref "U6") (pin "4") (pinfunction "COLLECTOR_4") (pintype "passive"))
      (node (ref "U7") (pin "4") (pinfunction "COLLECTOR_4") (pintype "passive"))
      (node (ref "U8") (pin "4") (pinfunction "COLLECTOR_4") (pintype "passive"))
      (node (ref "VA 1") (pin "1") (pinfunction "1_1") (pintype "passive"))
      (node (ref "VA 2") (pin "1") (pinfunction "1_1") (pintype "passive"))
    )
    (net (code "33") (name "Net-(IC1-A2)") (class "Default")
      (node (ref "IC1") (pin "6") (pinfunction "A2_6") (pintype "passive"))
      (node (ref "R4") (pin "2") (pinfunction "2_2") (pintype "passive"))
    )
    (net (code "34") (name "Net-(IC1-C)") (class "Default")
      (node (ref "IC1") (pin "2") (pinfunction "C_2") (pintype "passive"))
      (node (ref "R5") (pin "2") (pinfunction "2_2") (pintype "passive"))
    )
    (net (code "35") (name "Net-(IC2-A2)") (class "Default")
      (node (ref "IC2") (pin "6") (pinfunction "A2_6") (pintype "passive"))
      (node (ref "R7") (pin "2") (pinfunction "2_2") (pintype "passive"))
    )
    (net (code "36") (name "Net-(IC2-C)") (class "Default")
      (node (ref "IC2") (pin "2") (pinfunction "C_2") (pintype "passive"))
      (node (ref "R8") (pin "2") (pinfunction "2_2") (pintype "passive"))
    )
    (net (code "37") (name "Net-(IC3-A2)") (class "Default")
      (node (ref "IC3") (pin "6") (pinfunction "A2_6") (pintype "passive"))
      (node (ref "R10") (pin "2") (pinfunction "2_2") (pintype "passive"))
    )
    (net (code "38") (name "Net-(IC3-C)") (class "Default")
      (node (ref "IC3") (pin "2") (pinfunction "C_2") (pintype "passive"))
      (node (ref "R11") (pin "2") (pinfunction "2_2") (pintype "passive"))
    )
    (net (code "39") (name "Net-(IC4-A2)") (class "Default")
      (node (ref "IC4") (pin "6") (pinfunction "A2_6") (pintype "passive"))
      (node (ref "R13") (pin "2") (pinfunction "2_2") (pintype "passive"))
    )
    (net (code "40") (name "Net-(IC4-C)") (class "Default")
      (node (ref "IC4") (pin "2") (pinfunction "C_2") (pintype "passive"))
      (node (ref "R14") (pin "2") (pinfunction "2_2") (pintype "passive"))
    )
    (net (code "41") (name "Net-(J1-Pad1)") (class "Default")
      (node (ref "J1") (pin "1") (pinfunction "1_1") (pintype "passive"))
      (node (ref "R6") (pin "1") (pinfunction "1_1") (pintype "passive"))
    )
    (net (code "42") (name "Net-(J3-Pad1)") (class "Default")
      (node (ref "J3") (pin "1") (pinfunction "1_1") (pintype "passive"))
      (node (ref "R9") (pin "1") (pinfunction "1_1") (pintype "passive"))
    )
    (net (code "43") (name "Net-(J5-Pad1)") (class "Default")
      (node (ref "J5") (pin "1") (pinfunction "1_1") (pintype "passive"))
      (node (ref "R12") (pin "1") (pinfunction "1_1") (pintype "passive"))
    )
    (net (code "44") (name "Net-(J7-Pad1)") (class "Default")
      (node (ref "J7") (pin "1") (pinfunction "1_1") (pintype "passive"))
      (node (ref "R15") (pin "1") (pinfunction "1_1") (pintype "passive"))
    )
    (net (code "45") (name "Net-(J9-Pad1)") (class "Default")
      (node (ref "J9") (pin "1") (pinfunction "1_1") (pintype "passive"))
      (node (ref "R20") (pin "2") (pinfunction "2_2") (pintype "passive"))
    )
    (net (code "46") (name "Net-(J10-Pad1)") (class "Default")
      (node (ref "J10") (pin "1") (pinfunction "1_1") (pintype "passive"))
      (node (ref "R25") (pin "2") (pinfunction "2_2") (pintype "passive"))
    )
    (net (code "47") (name "Net-(OUT-1-NEG)") (class "Default")
      (node (ref "OUT-1") (pin "N") (pinfunction "NEG_N") (pintype "passive"))
      (node (ref "Q2") (pin "3") (pinfunction "S_3") (pintype "passive"))
      (node (ref "R18") (pin "1") (pinfunction "1_1") (pintype "passive"))
    )
    (net (code "48") (name "Net-(OUT-1-POS)") (class "Default")
      (node (ref "OUT-1") (pin "P") (pinfunction "POS_P") (pintype "passive"))
      (node (ref "Q2") (pin "2") (pinfunction "D_2") (pintype "passive"))
    )
    (net (code "49") (name "Net-(OUT-2-NEG)") (class "Default")
      (node (ref "OUT-2") (pin "N") (pinfunction "NEG_N") (pintype "passive"))
      (node (ref "Q3") (pin "3") (pinfunction "S_3") (pintype "passive"))
      (node (ref "R23") (pin "1") (pinfunction "1_1") (pintype "passive"))
    )
    (net (code "50") (name "Net-(OUT-2-POS)") (class "Default")
      (node (ref "OUT-2") (pin "P") (pinfunction "POS_P") (pintype "passive"))
      (node (ref "Q3") (pin "2") (pinfunction "D_2") (pintype "passive"))
    )
    (net (code "51") (name "Net-(Q1-GND)") (class "Default")
      (node (ref "12V(-)") (pin "1") (pinfunction "1_1") (pintype "passive"))
      (node (ref "3.3V Reg") (pin "3") (pinfunction "3_3") (pintype "passive"))
      (node (ref "Boot") (pin "1") (pinfunction "1_1") (pintype "passive"))
      (node (ref "Boot") (pin "2") (pinfunction "2_2") (pintype "passive"))
      (node (ref "C1") (pin "N") (pinfunction "N_N") (pintype "passive"))
      (node (ref "C2") (pin "N") (pinfunction "N_N") (pintype "passive"))
      (node (ref "ESP32(1-14)") (pin "1") (pinfunction "1_1") (pintype "passive"))
      (node (ref "ESP32(27-40)") (pin "14") (pinfunction "14_14") (pintype "passive"))
      (node (ref "Fan 1") (pin "2") (pinfunction "2_2") (pintype "passive"))
      (node (ref "Fan 2") (pin "2") (pinfunction "2_2") (pintype "passive"))
      (node (ref "J10") (pin "2") (pinfunction "2_2") (pintype "passive"))
      (node (ref "J9") (pin "2") (pinfunction "2_2") (pintype "passive"))
      (node (ref "Power") (pin "2") (pinfunction "2_2") (pintype "passive"))
      (node (ref "Prog Pins") (pin "4") (pinfunction "4_4") (pintype "passive"))
      (node (ref "Q1") (pin "2") (pinfunction "GND_2") (pintype "power_in"))
      (node (ref "R16") (pin "2") (pinfunction "2_2") (pintype "passive"))
      (node (ref "R21") (pin "2") (pinfunction "2_2") (pintype "passive"))
      (node (ref "R3") (pin "1") (pinfunction "1_1") (pintype "passive"))
      (node (ref "Reset") (pin "1") (pinfunction "1_1") (pintype "passive"))
      (node (ref "Reset") (pin "2") (pinfunction "2_2") (pintype "passive"))
      (node (ref "U1") (pin "3") (pinfunction "EMITTER_3") (pintype "passive"))
      (node (ref "U2") (pin "3") (pinfunction "EMITTER_3") (pintype "passive"))
      (node (ref "U3") (pin "3") (pinfunction "EMITTER_3") (pintype "passive"))
      (node (ref "U4") (pin "3") (pinfunction "EMITTER_3") (pintype "passive"))
      (node (ref "U6") (pin "2") (pinfunction "CATHODE_2") (pintype "passive"))
      (node (ref "U8") (pin "2") (pinfunction "CATHODE_2") (pintype "passive"))
      (node (ref "VA 1") (pin "2") (pinfunction "2_2") (pintype "passive"))
      (node (ref "VA 2") (pin "2") (pinfunction "2_2") (pintype "passive"))
    )
    (net (code "52") (name "Net-(Q1-OUT)") (class "Default")
      (node (ref "3.3V Reg") (pin "1") (pinfunction "1_1") (pintype "passive"))
      (node (ref "Q1") (pin "3") (pinfunction "OUT_3") (pintype "output"))
    )
    (net (code "53") (name "Net-(Q2-G)") (class "Default")
      (node (ref "Q2") (pin "1") (pinfunction "G_1") (pintype "passive"))
      (node (ref "R17") (pin "1") (pinfunction "1_1") (pintype "passive"))
      (node (ref "R18") (pin "2") (pinfunction "2_2") (pintype "passive"))
    )
    (net (code "54") (name "Net-(Q3-G)") (class "Default")
      (node (ref "Q3") (pin "1") (pinfunction "G_1") (pintype "passive"))
      (node (ref "R22") (pin "1") (pinfunction "1_1") (pintype "passive"))
      (node (ref "R23") (pin "2") (pinfunction "2_2") (pintype "passive"))
    )
    (net (code "55") (name "Net-(U1-ANODE)") (class "Default")
      (node (ref "R26") (pin "2") (pinfunction "2_2") (pintype "passive"))
      (node (ref "U1") (pin "1") (pinfunction "ANODE_1") (pintype "passive"))
    )
    (net (code "56") (name "Net-(U1-CATHODE)") (class "Default")
      (node (ref "U1") (pin "2") (pinfunction "CATHODE_2") (pintype "passive"))
      (node (ref "U2") (pin "2") (pinfunction "CATHODE_2") (pintype "passive"))
      (node (ref "U3") (pin "2") (pinfunction "CATHODE_2") (pintype "passive"))
      (node (ref "U4") (pin "2") (pinfunction "CATHODE_2") (pintype "passive"))
    )
    (net (code "57") (name "Net-(U1-COLLECTOR)") (class "Default")
      (node (ref "J1") (pin "2") (pinfunction "2_2") (pintype "passive"))
      (node (ref "R5") (pin "1") (pinfunction "1_1") (pintype "passive"))
      (node (ref "U1") (pin "4") (pinfunction "COLLECTOR_4") (pintype "passive"))
    )
    (net (code "58") (name "Net-(U2-ANODE)") (class "Default")
      (node (ref "R27") (pin "2") (pinfunction "2_2") (pintype "passive"))
      (node (ref "U2") (pin "1") (pinfunction "ANODE_1") (pintype "passive"))
    )
    (net (code "59") (name "Net-(U2-COLLECTOR)") (class "Default")
      (node (ref "J3") (pin "2") (pinfunction "2_2") (pintype "passive"))
      (node (ref "R8") (pin "1") (pinfunction "1_1") (pintype "passive"))
      (node (ref "U2") (pin "4") (pinfunction "COLLECTOR_4") (pintype "passive"))
    )
    (net (code "60") (name "Net-(U3-ANODE)") (class "Default")
      (node (ref "R28") (pin "2") (pinfunction "2_2") (pintype "passive"))
      (node (ref "U3") (pin "1") (pinfunction "ANODE_1") (pintype "passive"))
    )
    (net (code "61") (name "Net-(U3-COLLECTOR)") (class "Default")
      (node (ref "J5") (pin "2") (pinfunction "2_2") (pintype "passive"))
      (node (ref "R11") (pin "1") (pinfunction "1_1") (pintype "passive"))
      (node (ref "U3") (pin "4") (pinfunction "COLLECTOR_4") (pintype "passive"))
    )
    (net (code "62") (name "Net-(U4-ANODE)") (class "Default")
      (node (ref "R29") (pin "2") (pinfunction "2_2") (pintype "passive"))
      (node (ref "U4") (pin "1") (pinfunction "ANODE_1") (pintype "passive"))
    )
    (net (code "63") (name "Net-(U4-COLLECTOR)") (class "Default")
      (node (ref "J7") (pin "2") (pinfunction "2_2") (pintype "passive"))
      (node (ref "R14") (pin "1") (pinfunction "1_1") (pintype "passive"))
      (node (ref "U4") (pin "4") (pinfunction "COLLECTOR_4") (pintype "passive"))
    )
    (net (code "64") (name "Net-(U5-ANODE)") (class "Default")
      (node (ref "ESP32(1-14)") (pin "9") (pinfunction "9_9") (pintype "passive"))
      (node (ref "U5") (pin "1") (pinfunction "ANODE_1") (pintype "passive"))
    )
    (net (code "65") (name "Net-(U5-CATHODE)") (class "Default")
      (node (ref "R16") (pin "1") (pinfunction "1_1") (pintype "passive"))
      (node (ref "U5") (pin "2") (pinfunction "CATHODE_2") (pintype "passive"))
    )
    (net (code "66") (name "Net-(U5-EMITTER)") (class "Default")
      (node (ref "R17") (pin "2") (pinfunction "2_2") (pintype "passive"))
      (node (ref "R19") (pin "2") (pinfunction "2_2") (pintype "passive"))
      (node (ref "U5") (pin "3") (pinfunction "EMITTER_3") (pintype "passive"))
    )
    (net (code "67") (name "Net-(U6-ANODE)") (class "Default")
      (node (ref "R19") (pin "1") (pinfunction "1_1") (pintype "passive"))
      (node (ref "U6") (pin "1") (pinfunction "ANODE_1") (pintype "passive"))
    )
    (net (code "68") (name "Net-(U6-EMITTER)") (class "Default")
      (node (ref "R20") (pin "1") (pinfunction "1_1") (pintype "passive"))
      (node (ref "U6") (pin "3") (pinfunction "EMITTER_3") (pintype "passive"))
    )
    (net (code "69") (name "Net-(U7-ANODE)") (class "Default")
      (node (ref "ESP32(1-14)") (pin "10") (pinfunction "10_10") (pintype "passive"))
      (node (ref "U7") (pin "1") (pinfunction "ANODE_1") (pintype "passive"))
    )
    (net (code "70") (name "Net-(U7-CATHODE)") (class "Default")
      (node (ref "R21") (pin "1") (pinfunction "1_1") (pintype "passive"))
      (node (ref "U7") (pin "2") (pinfunction "CATHODE_2") (pintype "passive"))
    )
    (net (code "71") (name "Net-(U7-EMITTER)") (class "Default")
      (node (ref "R22") (pin "2") (pinfunction "2_2") (pintype "passive"))
      (node (ref "R24") (pin "2") (pinfunction "2_2") (pintype "passive"))
      (node (ref "U7") (pin "3") (pinfunction "EMITTER_3") (pintype "passive"))
    )
    (net (code "72") (name "Net-(U8-ANODE)") (class "Default")
      (node (ref "R24") (pin "1") (pinfunction "1_1") (pintype "passive"))
      (node (ref "U8") (pin "1") (pinfunction "ANODE_1") (pintype "passive"))
    )
    (net (code "73") (name "Net-(U8-EMITTER)") (class "Default")
      (node (ref "R25") (pin "1") (pinfunction "1_1") (pintype "passive"))
      (node (ref "U8") (pin "3") (pinfunction "EMITTER_3") (pintype "passive"))
    )
    (net (code "74") (name "unconnected-(ESP32(1-14)-Pad11)") (class "Default")
      (node (ref "ESP32(1-14)") (pin "11") (pinfunction "11_11") (pintype "passive"))
    )
    (net (code "75") (name "unconnected-(ESP32(1-14)-Pad12)") (class "Default")
      (node (ref "ESP32(1-14)") (pin "12") (pinfunction "12_12") (pintype "passive"))
    )
    (net (code "76") (name "unconnected-(ESP32(1-14)-Pad13)") (class "Default")
      (node (ref "ESP32(1-14)") (pin "13") (pinfunction "13_13") (pintype "passive"))
    )
    (net (code "77") (name "unconnected-(ESP32(1-14)-Pad14)") (class "Default")
      (node (ref "ESP32(1-14)") (pin "14") (pinfunction "14_14") (pintype "passive"))
    )
    (net (code "78") (name "unconnected-(ESP32(27-40)-Pad6)") (class "Default")
      (node (ref "ESP32(27-40)") (pin "6") (pinfunction "6_6") (pintype "passive"))
    )
    (net (code "79") (name "unconnected-(ESP32(27-40)-Pad7)") (class "Default")
      (node (ref "ESP32(27-40)") (pin "7") (pinfunction "7_7") (pintype "passive"))
    )
    (net (code "80") (name "unconnected-(IC1-P$1-Pad3)") (class "Default")
      (node (ref "IC1") (pin "3") (pinfunction "P$1_3") (pintype "open_collector"))
    )
    (net (code "81") (name "unconnected-(IC1-P$2-Pad5)") (class "Default")
      (node (ref "IC1") (pin "5") (pinfunction "P$2_5") (pintype "open_collector"))
    )
    (net (code "82") (name "unconnected-(IC2-P$1-Pad3)") (class "Default")
      (node (ref "IC2") (pin "3") (pinfunction "P$1_3") (pintype "open_collector"))
    )
    (net (code "83") (name "unconnected-(IC2-P$2-Pad5)") (class "Default")
      (node (ref "IC2") (pin "5") (pinfunction "P$2_5") (pintype "open_collector"))
    )
    (net (code "84") (name "unconnected-(IC3-P$1-Pad3)") (class "Default")
      (node (ref "IC3") (pin "3") (pinfunction "P$1_3") (pintype "open_collector"))
    )
    (net (code "85") (name "unconnected-(IC3-P$2-Pad5)") (class "Default")
      (node (ref "IC3") (pin "5") (pinfunction "P$2_5") (pintype "open_collector"))
    )
    (net (code "86") (name "unconnected-(IC4-P$1-Pad3)") (class "Default")
      (node (ref "IC4") (pin "3") (pinfunction "P$1_3") (pintype "open_collector"))
    )
    (net (code "87") (name "unconnected-(IC4-P$2-Pad5)") (class "Default")
      (node (ref "IC4") (pin "5") (pinfunction "P$2_5") (pintype "open_collector"))
    )
  )
)
